# LiPo_Charger.net
KiCad netlist of a schematic drawn in Altium Designer
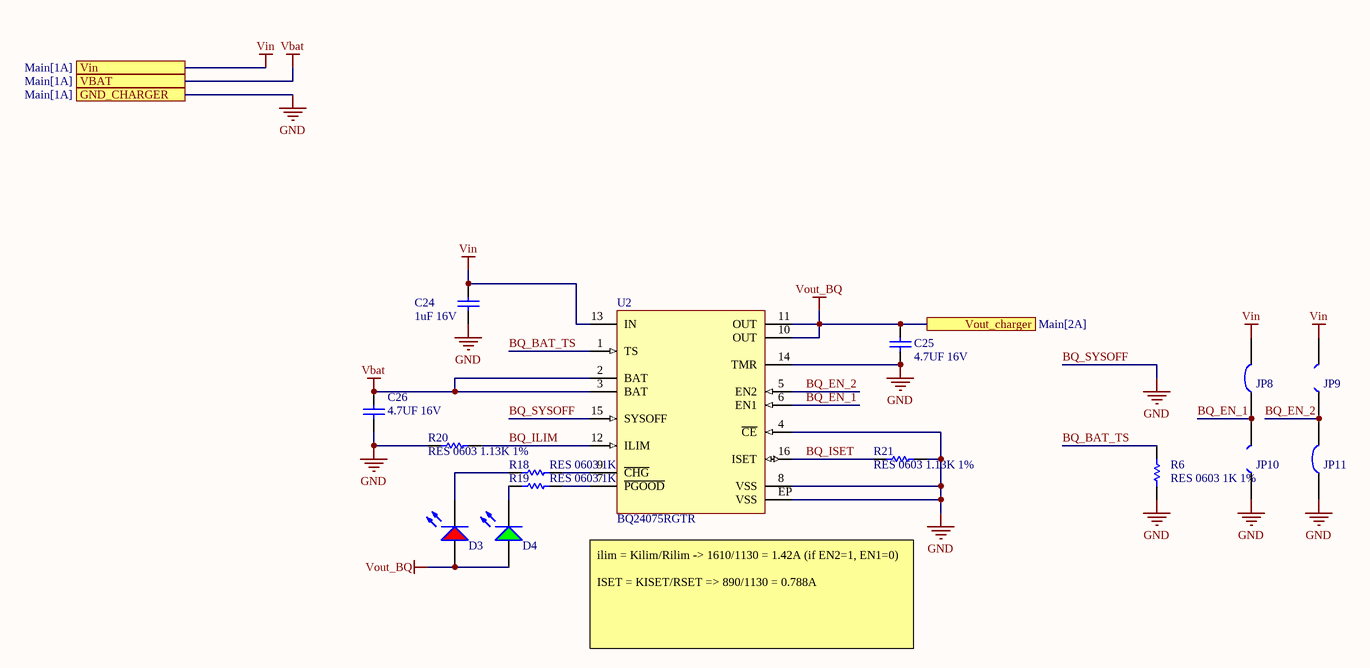
[diagram p0: LiPo_Charger.SchDoc]

(export (version "E")
  (design (tool "Eeschema 10.0.6"))
  (components
    (comp (ref "C24")
      (value "1uF 16V")
      (footprint "0603_CAP")
      (description "Capacitor Surface Mount 0603 Footprint 1UF 16V 10% Tolerance Ceramic X7R")
      (fields (field (name "TOLERANCE") "10%") (field (name "MANUFACTURER") "Various"))
      (libsource (lib "University of Pennsylvania (ESE Labs)") (part "cap"))
    )
    (comp (ref "C25")
      (value "4.7UF 16V")
      (footprint "0805_CAP")
      (description "Capacitor Surface Mount 0805 Footprint 4.7UF 16V 10% Tolerance Ceramic X7R")
      (fields (field (name "MANUFACTURER") "Various") (field (name "VOLTAGE") "16V"))
      (libsource (lib "University of Pennsylvania (ESE Labs)") (part "cap"))
    )
    (comp (ref "C26")
      (value "4.7UF 16V")
      (footprint "0805_CAP")
      (description "Capacitor Surface Mount 0805 Footprint 4.7UF 16V 10% Tolerance Ceramic X7R")
      (fields (field (name "MANUFACTURER") "Various") (field (name "VOLTAGE") "16V"))
      (libsource (lib "University of Pennsylvania (ESE Labs)") (part "cap"))
    )
    (comp (ref "D3")
      (value "LSM0805412V")
      (footprint "LED_0805_RED")
      (description "Single Color LED, RED, 0805")
      (libsource (lib "University of Pennsylvania (ESE Labs)") (part "LED-RED-AK-2"))
    )
    (comp (ref "D4")
      (value "LSM0805452V")
      (footprint "LED_0805")
      (description "Single Color LED, Green, 0805")
      (libsource (lib "University of Pennsylvania (ESE Labs)") (part "LED-GREEN-AK-2"))
    )
    (comp (ref "JP8")
      (value "0603 link")
      (footprint "0603_JP_RES")
      (description "0O link, SMD, 0603, Solder Bridge Option")
      (fields (field (name "MANUFACTURER") "Generic") (field (name "SOURCE") "Shunts and Jumpers.SchLib"))
      (libsource (lib "") (part "CMP-ROOT-0007-1_1"))
    )
    (comp (ref "JP9")
      (value "0603 link (Open)")
      (footprint "0603_JP_Open")
      (description "0O link, Solder Bridge/SMD, Open")
      (fields (field (name "SOURCE") "Shunts and Jumpers.SchLib"))
      (libsource (lib "") (part "CMP-ROOT-0012-1_1"))
    )
    (comp (ref "JP10")
      (value "0603 link (Open)")
      (footprint "0603_JP_Open")
      (description "0O link, Solder Bridge/SMD, Open")
      (fields (field (name "SOURCE") "Shunts and Jumpers.SchLib"))
      (libsource (lib "University of Pennsylvania (ESE)") (part "CMP-ROOT-0012-1"))
    )
    (comp (ref "JP11")
      (value "0603 link")
      (footprint "0603_JP_RES")
      (description "0O link, SMD, 0603, Solder Bridge Option")
      (fields (field (name "MANUFACTURER") "Generic") (field (name "SOURCE") "Shunts and Jumpers.SchLib"))
      (libsource (lib "University of Pennsylvania (ESE)") (part "CMP-ROOT-0007-1"))
    )
    (comp (ref "R6")
      (value "RES 0603 1K 1%")
      (footprint "0603_RES")
      (description "Resistor Surface Mount, 1K Ohms, 0603 Footprint, 1% Tolerance 0.1W")
      (fields (field (name "MANUFACTURER") "Various") (field (name "TOLERANCE") "1%"))
      (libsource (lib "University of Pennsylvania (ESE)") (part "res"))
    )
    (comp (ref "R18")
      (value "RES 0603 1K 1%")
      (footprint "0603_RES")
      (description "Resistor Surface Mount, 1K Ohms, 0603 Footprint, 1% Tolerance 0.1W")
      (fields (field (name "MANUFACTURER") "Various") (field (name "TOLERANCE") "1%"))
      (libsource (lib "University of Pennsylvania (ESE)") (part "res"))
    )
    (comp (ref "R19")
      (value "RES 0603 1K 1%")
      (footprint "0603_RES")
      (description "Resistor Surface Mount, 1K Ohms, 0603 Footprint, 1% Tolerance 0.1W")
      (fields (field (name "MANUFACTURER") "Various") (field (name "TOLERANCE") "1%"))
      (libsource (lib "University of Pennsylvania (ESE)") (part "res"))
    )
    (comp (ref "R20")
      (value "RES 0603 1.13K 1%")
      (footprint "0603_RES")
      (description "Resistor Surface Mount, 1.13K Ohms, 0603 Footprint, 1% Tolerance 0.1W")
      (fields (field (name "MANUFACTURER") "Various") (field (name "TOLERANCE") "1%"))
      (libsource (lib "University of Pennsylvania (ESE)") (part "res"))
    )
    (comp (ref "R21")
      (value "RES 0603 1.13K 1%")
      (footprint "0603_RES")
      (description "Resistor Surface Mount, 1.13K Ohms, 0603 Footprint, 1% Tolerance 0.1W")
      (fields (field (name "MANUFACTURER") "Various") (field (name "TOLERANCE") "1%"))
      (libsource (lib "University of Pennsylvania (ESE)") (part "res"))
    )
    (comp (ref "U2")
      (value "BQ24075RGTR")
      (footprint "FP-RGT0016C-IPC_A")
      (description "Power Supply Support Circuit, Adjustable, 1 Channel, 6.6, PQCC16")
      (libsource (lib "University of Pennsylvania (ESE)") (part "273aa663c5dc25a29e76a3da5be16cc"))
    )
  )
  (nets
    (net (code "1") (name "/BQ_BAT_TS") (class "Default")
      (node (ref "R6") (pin "2") (pinfunction "2_2") (pintype "passive"))
      (node (ref "U2") (pin "1") (pinfunction "TS_1") (pintype "input"))
    )
    (net (code "2") (name "/BQ_EN_1") (class "Default")
      (node (ref "JP10") (pin "2") (pinfunction "2_2") (pintype "passive"))
      (node (ref "JP8") (pin "1") (pinfunction "1_1") (pintype "passive"))
      (node (ref "U2") (pin "6") (pinfunction "EN1_6") (pintype "input"))
    )
    (net (code "3") (name "/BQ_EN_2") (class "Default")
      (node (ref "JP11") (pin "1") (pinfunction "1_1") (pintype "passive"))
      (node (ref "JP9") (pin "2") (pinfunction "2_2") (pintype "passive"))
      (node (ref "U2") (pin "5") (pinfunction "EN2_5") (pintype "input"))
    )
    (net (code "4") (name "/BQ_ILIM") (class "Default")
      (node (ref "R20") (pin "2") (pinfunction "2_2") (pintype "passive"))
      (node (ref "U2") (pin "12") (pinfunction "ILIM_12") (pintype "input"))
    )
    (net (code "5") (name "/BQ_ISET") (class "Default")
      (node (ref "R21") (pin "1") (pinfunction "1_1") (pintype "passive"))
      (node (ref "U2") (pin "16") (pinfunction "ISET_16") (pintype "bidirectional"))
    )
    (net (code "6") (name "GND") (class "Default")
      (node (ref "C24") (pin "1") (pinfunction "1_1") (pintype "passive"))
      (node (ref "C25") (pin "1") (pinfunction "1_1") (pintype "passive"))
      (node (ref "C26") (pin "1") (pinfunction "1_1") (pintype "passive"))
      (node (ref "JP10") (pin "1") (pinfunction "1_1") (pintype "passive"))
      (node (ref "JP11") (pin "2") (pinfunction "2_2") (pintype "passive"))
      (node (ref "R20") (pin "1") (pinfunction "1_1") (pintype "passive"))
      (node (ref "R21") (pin "2") (pinfunction "2_2") (pintype "passive"))
      (node (ref "R6") (pin "1") (pinfunction "1_1") (pintype "passive"))
      (node (ref "U2") (pin "14") (pinfunction "TMR_14") (pintype "passive"))
      (node (ref "U2") (pin "15") (pinfunction "SYSOFF_15") (pintype "input"))
      (node (ref "U2") (pin "4") (pinfunction "~{CE}_4") (pintype "input"))
      (node (ref "U2") (pin "8") (pinfunction "VSS_8") (pintype "power_in"))
      (node (ref "U2") (pin "EP") (pinfunction "VSS_EP") (pintype "power_in"))
    )
    (net (code "7") (name "Net-(D3-PadK)") (class "Default")
      (node (ref "D3") (pin "K") (pinfunction "K_K") (pintype "passive"))
      (node (ref "R18") (pin "2") (pinfunction "2_2") (pintype "passive"))
    )
    (net (code "8") (name "Net-(D4-PadK)") (class "Default")
      (node (ref "D4") (pin "K") (pinfunction "K_K") (pintype "passive"))
      (node (ref "R19") (pin "2") (pinfunction "2_2") (pintype "passive"))
    )
    (net (code "9") (name "Net-(U2-~{CHG})") (class "Default")
      (node (ref "R18") (pin "1") (pinfunction "1_1") (pintype "passive"))
      (node (ref "U2") (pin "9") (pinfunction "~{CHG}_9") (pintype "tri_state"))
    )
    (net (code "10") (name "Net-(U2-~{PGOOD})") (class "Default")
      (node (ref "R19") (pin "1") (pinfunction "1_1") (pintype "passive"))
      (node (ref "U2") (pin "7") (pinfunction "~{PGOOD}_7") (pintype "tri_state"))
    )
    (net (code "11") (name "Vbat") (class "Default")
      (node (ref "C26") (pin "2") (pinfunction "2_2") (pintype "passive"))
      (node (ref "U2") (pin "2") (pinfunction "BAT_2") (pintype "power_in"))
      (node (ref "U2") (pin "3") (pinfunction "BAT_3") (pintype "power_in"))
    )
    (net (code "12") (name "Vin") (class "Default")
      (node (ref "C24") (pin "2") (pinfunction "2_2") (pintype "passive"))
      (node (ref "JP8") (pin "2") (pinfunction "2_2") (pintype "passive"))
      (node (ref "JP9") (pin "1") (pinfunction "1_1") (pintype "passive"))
      (node (ref "U2") (pin "13") (pinfunction "IN_13") (pintype "power_in"))
    )
    (net (code "13") (name "Vout_BQ") (class "Default")
      (node (ref "C25") (pin "2") (pinfunction "2_2") (pintype "passive"))
      (node (ref "D3") (pin "A") (pinfunction "A_A") (pintype "passive"))
      (node (ref "D4") (pin "A") (pinfunction "A_A") (pintype "passive"))
      (node (ref "U2") (pin "10") (pinfunction "OUT_10") (pintype "power_in"))
      (node (ref "U2") (pin "11") (pinfunction "OUT_11") (pintype "power_in"))
    )
  )
)
